# protection_DC.net
KiCad netlist of a schematic drawn in Altium Designer
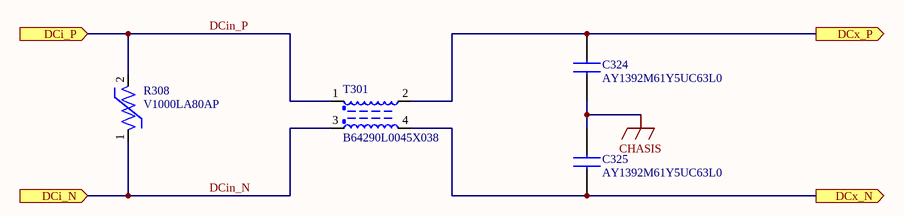
[diagram p0: protection_DC.SchDoc]

(export (version "E")
  (design (tool "Eeschema 10.0.6"))
  (components
    (comp (ref "C324")
      (value "AY1392M61Y5UC63L0")
      (footprint "AY1392M61Y5UC63L0")
      (description "Cap Ceramic 0.0039uF 1500V Y5U 20% Through Hole 10mm Radial 125°C Bulk")
      (fields (field (name "MANUFACTURER") "Vishay"))
      (libsource (lib "Altium_Library_POWERLAB") (part "AY1392M61Y5UC63L0"))
    )
    (comp (ref "C325")
      (value "AY1392M61Y5UC63L0")
      (footprint "AY1392M61Y5UC63L0")
      (description "Cap Ceramic 0.0039uF 1500V Y5U 20% Through Hole 10mm Radial 125°C Bulk")
      (fields (field (name "MANUFACTURER") "Vishay"))
      (libsource (lib "Altium_Library_POWERLAB") (part "AY1392M61Y5UC63L0"))
    )
    (comp (ref "R308")
      (value "V1000LA80AP")
      (footprint "V1000LA80AP")
      (description "Varistors 1000V 130pF")
      (fields (field (name "MANUFACTURER") "Littelfuse"))
      (libsource (lib "Altium_Library_POWERLAB") (part "V1000LA80AP"))
    )
    (comp (ref "T301")
      (value "B64290L0045X038")
      (footprint "B64290L0045X038")
      (description "FERRITE CORE TOROID 6.44UH T38")
      (fields (field (name "MANUFACTURER") "TDK"))
      (libsource (lib "Altium_Library_POWERLAB") (part "B64290L0045X038"))
    )
  )
  (nets
    (net (code "1") (name "/DCin_N") (class "Default")
      (node (ref "R308") (pin "1") (pinfunction "16_1") (pintype "passive"))
      (node (ref "T301") (pin "3") (pinfunction "3_3") (pintype "passive"))
    )
    (net (code "2") (name "/DCin_P") (class "Default")
      (node (ref "R308") (pin "2") (pinfunction "16_2") (pintype "passive"))
      (node (ref "T301") (pin "1") (pinfunction "1_1") (pintype "passive"))
    )
    (net (code "3") (name "/DCx_N") (class "Default")
      (node (ref "C325") (pin "2") (pinfunction "2_2") (pintype "passive"))
      (node (ref "T301") (pin "4") (pinfunction "4_4") (pintype "passive"))
    )
    (net (code "4") (name "/DCx_P") (class "Default")
      (node (ref "C324") (pin "1") (pinfunction "1_1") (pintype "passive"))
      (node (ref "T301") (pin "2") (pinfunction "2_2") (pintype "passive"))
    )
    (net (code "5") (name "CHASIS") (class "Default")
      (node (ref "C324") (pin "2") (pinfunction "2_2") (pintype "passive"))
      (node (ref "C325") (pin "1") (pinfunction "1_1") (pintype "passive"))
    )
  )
)
